# Sheet1.net
KiCad netlist of a schematic drawn in Altium Designer
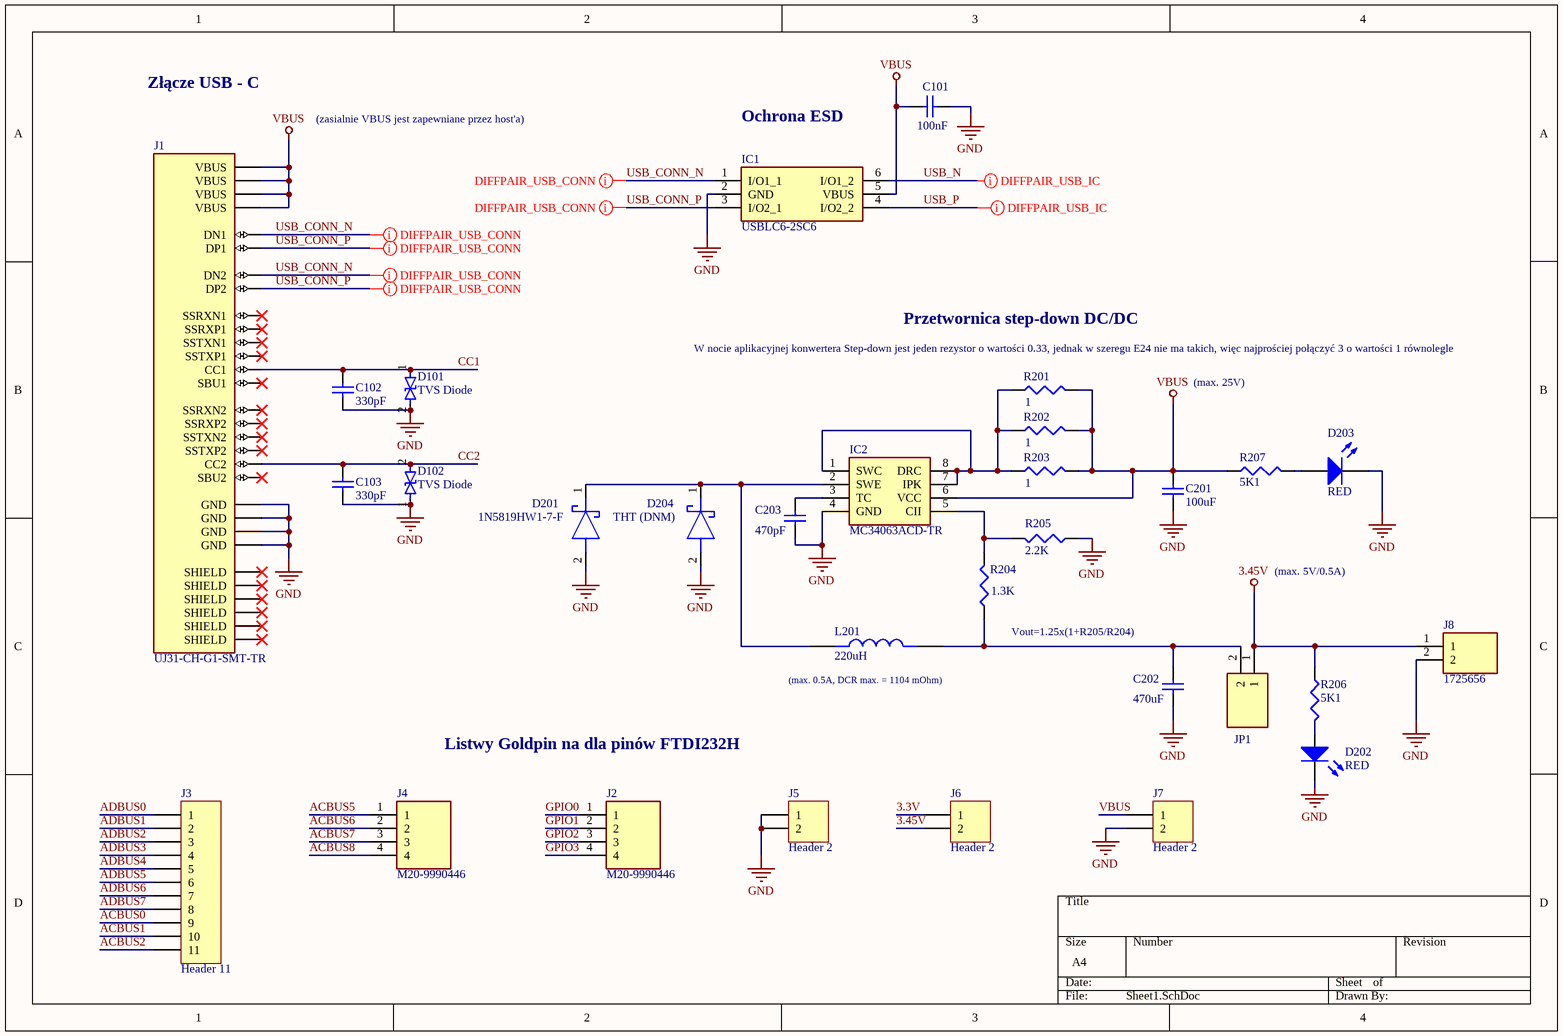
[diagram p0: Sheet1.SchDoc]

(export (version "E")
  (design (tool "Eeschema 10.0.6"))
  (components
    (comp (ref "C101")
      (value "100nF")
      (footprint "1608[0603]")
      (description "Capacitor (Semiconductor SIM Model)")
      (fields (field (name "Comment") "Cap Semi") (field (name "PUBLISHER") "Altium Limited"))
      (libsource (lib "Miscellaneous Devices") (part "Cap Semi"))
    )
    (comp (ref "C102")
      (value "330pF")
      (footprint "1608[0603]")
      (description "Capacitor (Semiconductor SIM Model)")
      (fields (field (name "Comment") "Cap Semi") (field (name "PUBLISHER") "Altium Limited"))
      (libsource (lib "Miscellaneous Devices") (part "Cap Semi"))
    )
    (comp (ref "C103")
      (value "330pF")
      (footprint "1608[0603]")
      (description "Capacitor (Semiconductor SIM Model)")
      (fields (field (name "Comment") "Cap Semi") (field (name "PUBLISHER") "Altium Limited"))
      (libsource (lib "Miscellaneous Devices") (part "Cap Semi"))
    )
    (comp (ref "C201")
      (value "100uF")
      (footprint "1608[0603]")
      (description "Capacitor (Semiconductor SIM Model)")
      (fields (field (name "Comment") "Cap Semi") (field (name "PUBLISHER") "Altium Limited"))
      (libsource (lib "Miscellaneous Devices") (part "Cap Semi"))
    )
    (comp (ref "C202")
      (value "470uF")
      (footprint "1608[0603]")
      (description "Capacitor (Semiconductor SIM Model)")
      (fields (field (name "Comment") "Cap Semi") (field (name "PUBLISHER") "Altium Limited"))
      (libsource (lib "Miscellaneous Devices") (part "Cap Semi"))
    )
    (comp (ref "C203")
      (value "470pF")
      (footprint "1608[0603]")
      (description "Capacitor (Semiconductor SIM Model)")
      (fields (field (name "Comment") "Cap Semi") (field (name "PUBLISHER") "Altium Limited"))
      (libsource (lib "Miscellaneous Devices") (part "Cap Semi"))
    )
    (comp (ref "D101")
      (value "TVS Diode")
      (footprint "PESD15VW1BCSF - TVS Diode")
      (description "PESD15VW1BCSFYL - Extremely low capacitance bidirectional ESD protection diode")
      (libsource (lib "Schlib1") (part "PESD15VW1BCSFYL"))
    )
    (comp (ref "D102")
      (value "TVS Diode")
      (footprint "PESD15VW1BCSF - TVS Diode")
      (description "PESD15VW1BCSFYL - Extremely low capacitance bidirectional ESD protection diode")
      (libsource (lib "Schlib1") (part "PESD15VW1BCSFYL"))
    )
    (comp (ref "D201")
      (value "1N5819HW1-7-F")
      (footprint "SODFL3518X115N")
      (description "Schottky Diode")
      (fields (field (name "MOUSER PART NUMBER") "621-1N5819HW1-7-F"))
      (libsource (lib "Schlib1") (part "1N5819HW1-7-F"))
    )
    (comp (ref "D202")
      (value "RED")
      (footprint "LEDC2012X80N")
      (description "Typical RED, GREEN, YELLOW, AMBER GaAs LED")
      (fields (field (name "PUBLISHER") "Altium Limited"))
      (libsource (lib "Miscellaneous Devices") (part "LED2"))
    )
    (comp (ref "D203")
      (value "RED")
      (footprint "LEDC2012X80N")
      (description "Typical RED, GREEN, YELLOW, AMBER GaAs LED")
      (fields (field (name "PUBLISHER") "Altium Limited"))
      (libsource (lib "Miscellaneous Devices") (part "LED2"))
    )
    (comp (ref "D204")
      (value "THT (DNM)")
      (footprint "DIOAD1796W86L628D292")
      (description "Schottky Diode")
      (fields
        (field (name "MANUFACTURER_PART_NUMBER") "1N5819HW1-7-F")
        (field (name "MOUSER PART NUMBER") "621-1N5819HW1-7-F")
      )
      (libsource (lib "Schlib1") (part "1N5819HW1-7-F"))
    )
    (comp (ref "IC1")
      (value "USBLC6-2SC6")
      (footprint "SOT95P280X145-6N")
      (description "Integrated Circuit")
      (fields (field (name "MOUSER PART NUMBER") "511-USBLC6-2SC6"))
      (libsource (lib "Schlib1") (part "USBLC6-2SC6"))
    )
    (comp (ref "IC2")
      (value "MC34063ACD-TR")
      (footprint "SOIC127P600X175-8N")
      (description "Integrated Circuit")
      (fields (field (name "MOUSER PART NUMBER") "511-MC34063ACD-TR"))
      (libsource (lib "Schlib1") (part "MC34063ACD-TR"))
    )
    (comp (ref "J1")
      (value "UJ31-CH-G1-SMT-TR")
      (footprint "CUI_UJ31-CH-G1-SMT-TR - duplicate")
      (description "Type C, USB 3.1 Gen 2, 5 A, Right Angle, Surface Mount _SMT_ , USB Receptacle")
      (fields (field (name "MF") "CUI Devices"))
      (libsource (lib "Schlib1") (part "UJ31-CH-G1-SMT-TR"))
    )
    (comp (ref "J2")
      (value "M20-9990446")
      (footprint "HDRV4W64P0X254_1X4_1016X254X889P")
      (description "Connector")
      (fields (field (name "MOUSER PART NUMBER") "855-M20-9990446"))
      (libsource (lib "Schlib1") (part "M20-9990446"))
    )
    (comp (ref "J3")
      (value "Header 11")
      (footprint "HDR1X11")
      (description "Header, 11-Pin")
      (fields (field (name "PUBLISHER") "Altium Limited"))
      (libsource (lib "Miscellaneous Connectors") (part "Header 11"))
    )
    (comp (ref "J4")
      (value "M20-9990446")
      (footprint "HDRV4W64P0X254_1X4_1016X254X889P")
      (description "Connector")
      (fields (field (name "MOUSER PART NUMBER") "855-M20-9990446"))
      (libsource (lib "Schlib1") (part "M20-9990446"))
    )
    (comp (ref "J5")
      (value "Header 2")
      (footprint "HDR1X2")
      (description "Header, 2-Pin")
      (fields (field (name "PUBLISHER") "Altium Limited"))
      (libsource (lib "Miscellaneous Connectors") (part "Header 2"))
    )
    (comp (ref "J6")
      (value "Header 2")
      (footprint "HDR1X2")
      (description "Header, 2-Pin")
      (fields (field (name "PUBLISHER") "Altium Limited"))
      (libsource (lib "Miscellaneous Connectors") (part "Header 2"))
    )
    (comp (ref "J7")
      (value "Header 2")
      (footprint "HDR1X2")
      (description "Header, 2-Pin")
      (fields (field (name "PUBLISHER") "Altium Limited"))
      (libsource (lib "Miscellaneous Connectors") (part "Header 2"))
    )
    (comp (ref "J8")
      (value "1725656")
      (footprint "SamacSys:1725656")
      (description "Screw terminal")
      (fields (field (name "MOUSER PART NUMBER") "651-1725656"))
      (libsource (lib "Schlib1") (part "1725656"))
    )
    (comp (ref "JP1")
      (value "5-146277-2")
      (footprint "HDRV2W67P0X254_1X2_467X234X823P")
      (description "Connector")
      (fields (field (name "MOUSER PART NUMBER") "571-5-146277-2"))
      (libsource (lib "Schlib1") (part "5-146277-2"))
    )
    (comp (ref "L201")
      (value "220uH")
      (footprint "242418 FPS")
      (description "Inductor 220uH, tolerance=20%, max. current=0.5A, DCR max. = 1104 mOhm")
      (libsource (lib "Schlib1") (part "242418FPS-221M-01"))
    )
    (comp (ref "R201")
      (value "1")
      (footprint "RESC1608X55N")
      (description "Resistor")
      (fields (field (name "Comment") "Res3") (field (name "PUBLISHER") "Altium Limited"))
      (libsource (lib "Miscellaneous Devices") (part "Res3"))
    )
    (comp (ref "R202")
      (value "1")
      (footprint "RESC1608X55N")
      (description "Resistor")
      (fields (field (name "Comment") "Res3") (field (name "PUBLISHER") "Altium Limited"))
      (libsource (lib "Miscellaneous Devices") (part "Res3"))
    )
    (comp (ref "R203")
      (value "1")
      (footprint "RESC1608X55N")
      (description "Resistor")
      (fields (field (name "Comment") "Res3") (field (name "PUBLISHER") "Altium Limited"))
      (libsource (lib "Miscellaneous Devices") (part "Res3"))
    )
    (comp (ref "R204")
      (value "1.3K")
      (footprint "RESC1608X55N")
      (description "Resistor")
      (fields (field (name "Comment") "Res3") (field (name "PUBLISHER") "Altium Limited"))
      (libsource (lib "Miscellaneous Devices") (part "Res3"))
    )
    (comp (ref "R205")
      (value "2.2K")
      (footprint "RESC1608X55N")
      (description "Resistor")
      (fields (field (name "Comment") "Res3") (field (name "PUBLISHER") "Altium Limited"))
      (libsource (lib "Miscellaneous Devices") (part "Res3"))
    )
    (comp (ref "R206")
      (value "5K1")
      (footprint "RESC1608X55N")
      (description "Resistor")
      (fields (field (name "Comment") "Res3") (field (name "PUBLISHER") "Altium Limited"))
      (libsource (lib "Miscellaneous Devices") (part "Res3"))
    )
    (comp (ref "R207")
      (value "5K1")
      (footprint "RESC1608X55N")
      (description "Resistor")
      (fields (field (name "Comment") "Res3") (field (name "PUBLISHER") "Altium Limited"))
      (libsource (lib "Miscellaneous Devices") (part "Res3"))
    )
  )
  (nets
    (net (code "1") (name "/3.3V") (class "Default")
      (node (ref "J6") (pin "1") (pinfunction "1_1") (pintype "passive"))
    )
    (net (code "2") (name "/ACBUS0") (class "Default")
      (node (ref "J3") (pin "9") (pinfunction "9_9") (pintype "passive"))
    )
    (net (code "3") (name "/ACBUS1") (class "Default")
      (node (ref "J3") (pin "10") (pinfunction "10_10") (pintype "passive"))
    )
    (net (code "4") (name "/ACBUS2") (class "Default")
      (node (ref "J3") (pin "11") (pinfunction "11_11") (pintype "passive"))
    )
    (net (code "5") (name "/ACBUS5") (class "Default")
      (node (ref "J4") (pin "1") (pinfunction "1_1") (pintype "passive"))
    )
    (net (code "6") (name "/ACBUS6") (class "Default")
      (node (ref "J4") (pin "2") (pinfunction "2_2") (pintype "passive"))
    )
    (net (code "7") (name "/ACBUS7") (class "Default")
      (node (ref "J4") (pin "3") (pinfunction "3_3") (pintype "passive"))
    )
    (net (code "8") (name "/ACBUS8") (class "Default")
      (node (ref "J4") (pin "4") (pinfunction "4_4") (pintype "passive"))
    )
    (net (code "9") (name "/ADBUS0") (class "Default")
      (node (ref "J3") (pin "1") (pinfunction "1_1") (pintype "passive"))
    )
    (net (code "10") (name "/ADBUS1") (class "Default")
      (node (ref "J3") (pin "2") (pinfunction "2_2") (pintype "passive"))
    )
    (net (code "11") (name "/ADBUS2") (class "Default")
      (node (ref "J3") (pin "3") (pinfunction "3_3") (pintype "passive"))
    )
    (net (code "12") (name "/ADBUS3") (class "Default")
      (node (ref "J3") (pin "4") (pinfunction "4_4") (pintype "passive"))
    )
    (net (code "13") (name "/ADBUS4") (class "Default")
      (node (ref "J3") (pin "5") (pinfunction "5_5") (pintype "passive"))
    )
    (net (code "14") (name "/ADBUS5") (class "Default")
      (node (ref "J3") (pin "6") (pinfunction "6_6") (pintype "passive"))
    )
    (net (code "15") (name "/ADBUS6") (class "Default")
      (node (ref "J3") (pin "7") (pinfunction "7_7") (pintype "passive"))
    )
    (net (code "16") (name "/ADBUS7") (class "Default")
      (node (ref "J3") (pin "8") (pinfunction "8_8") (pintype "passive"))
    )
    (net (code "17") (name "/CC1") (class "Default")
      (node (ref "C102") (pin "2") (pinfunction "2_2") (pintype "passive"))
      (node (ref "D101") (pin "1") (pintype "passive"))
      (node (ref "J1") (pin "A5") (pinfunction "CC1_A5") (pintype "bidirectional"))
    )
    (net (code "18") (name "/CC2") (class "Default")
      (node (ref "C103") (pin "2") (pinfunction "2_2") (pintype "passive"))
      (node (ref "D102") (pin "2") (pintype "passive"))
      (node (ref "J1") (pin "B5") (pinfunction "CC2_B5") (pintype "bidirectional"))
    )
    (net (code "19") (name "/GPIO0") (class "Default")
      (node (ref "J2") (pin "1") (pinfunction "1_1") (pintype "passive"))
    )
    (net (code "20") (name "/GPIO1") (class "Default")
      (node (ref "J2") (pin "2") (pinfunction "2_2") (pintype "passive"))
    )
    (net (code "21") (name "/GPIO2") (class "Default")
      (node (ref "J2") (pin "3") (pinfunction "3_3") (pintype "passive"))
    )
    (net (code "22") (name "/GPIO3") (class "Default")
      (node (ref "J2") (pin "4") (pinfunction "4_4") (pintype "passive"))
    )
    (net (code "23") (name "/USB_CONN_N") (class "Default")
      (node (ref "IC1") (pin "1") (pinfunction "I/O1_1_1") (pintype "passive"))
      (node (ref "J1") (pin "A7") (pinfunction "DN1_A7") (pintype "bidirectional"))
      (node (ref "J1") (pin "B7") (pinfunction "DN2_B7") (pintype "bidirectional"))
    )
    (net (code "24") (name "/USB_CONN_P") (class "Default")
      (node (ref "IC1") (pin "3") (pinfunction "I/O2_1_3") (pintype "passive"))
      (node (ref "J1") (pin "A6") (pinfunction "DP1_A6") (pintype "bidirectional"))
      (node (ref "J1") (pin "B6") (pinfunction "DP2_B6") (pintype "bidirectional"))
    )
    (net (code "25") (name "/USB_N") (class "Default")
      (node (ref "IC1") (pin "6") (pinfunction "I/O1_2_6") (pintype "passive"))
    )
    (net (code "26") (name "/USB_P") (class "Default")
      (node (ref "IC1") (pin "4") (pinfunction "I/O2_2_4") (pintype "passive"))
    )
    (net (code "27") (name "3.45V") (class "Default")
      (node (ref "J6") (pin "2") (pinfunction "2_2") (pintype "passive"))
      (node (ref "J8") (pin "1") (pinfunction "1_1") (pintype "passive"))
      (node (ref "JP1") (pin "1") (pinfunction "1_1") (pintype "passive"))
      (node (ref "R206") (pin "1") (pinfunction "1_1") (pintype "passive"))
    )
    (net (code "28") (name "GND") (class "Default")
      (node (ref "C101") (pin "2") (pinfunction "2_2") (pintype "passive"))
      (node (ref "C102") (pin "1") (pinfunction "1_1") (pintype "passive"))
      (node (ref "C103") (pin "1") (pinfunction "1_1") (pintype "passive"))
      (node (ref "C201") (pin "1") (pinfunction "1_1") (pintype "passive"))
      (node (ref "C202") (pin "1") (pinfunction "1_1") (pintype "passive"))
      (node (ref "C203") (pin "1") (pinfunction "1_1") (pintype "passive"))
      (node (ref "D101") (pin "2") (pintype "passive"))
      (node (ref "D102") (pin "1") (pintype "passive"))
      (node (ref "D201") (pin "2") (pinfunction "A_2") (pintype "passive"))
      (node (ref "D202") (pin "2") (pinfunction "K_2") (pintype "passive"))
      (node (ref "D203") (pin "2") (pinfunction "K_2") (pintype "passive"))
      (node (ref "D204") (pin "2") (pinfunction "A_2") (pintype "passive"))
      (node (ref "IC1") (pin "2") (pinfunction "GND_2") (pintype "passive"))
      (node (ref "IC2") (pin "4") (pinfunction "GND_4") (pintype "passive"))
      (node (ref "J1") (pin "A1") (pinfunction "GND_A1") (pintype "power_in"))
      (node (ref "J1") (pin "A12") (pinfunction "GND_A12") (pintype "power_in"))
      (node (ref "J1") (pin "B1") (pinfunction "GND_B1") (pintype "power_in"))
      (node (ref "J1") (pin "B12") (pinfunction "GND_B12") (pintype "power_in"))
      (node (ref "J5") (pin "1") (pinfunction "1_1") (pintype "passive"))
      (node (ref "J5") (pin "2") (pinfunction "2_2") (pintype "passive"))
      (node (ref "J7") (pin "2") (pinfunction "2_2") (pintype "passive"))
      (node (ref "J8") (pin "2") (pinfunction "2_2") (pintype "passive"))
      (node (ref "R205") (pin "1") (pinfunction "1_1") (pintype "passive"))
    )
    (net (code "29") (name "Net-(C202-Pad2)") (class "Default")
      (node (ref "C202") (pin "2") (pinfunction "2_2") (pintype "passive"))
      (node (ref "JP1") (pin "2") (pinfunction "2_2") (pintype "passive"))
      (node (ref "L201") (pin "2") (pinfunction "2_2") (pintype "passive"))
      (node (ref "R204") (pin "1") (pinfunction "1_1") (pintype "passive"))
    )
    (net (code "30") (name "Net-(D201-K)") (class "Default")
      (node (ref "D201") (pin "1") (pinfunction "K_1") (pintype "passive"))
      (node (ref "D204") (pin "1") (pinfunction "K_1") (pintype "passive"))
      (node (ref "IC2") (pin "2") (pinfunction "SWE_2") (pintype "passive"))
      (node (ref "L201") (pin "1") (pinfunction "1_1") (pintype "passive"))
    )
    (net (code "31") (name "Net-(D202-A)") (class "Default")
      (node (ref "D202") (pin "1") (pinfunction "A_1") (pintype "passive"))
      (node (ref "R206") (pin "2") (pinfunction "2_2") (pintype "passive"))
    )
    (net (code "32") (name "Net-(D203-A)") (class "Default")
      (node (ref "D203") (pin "1") (pinfunction "A_1") (pintype "passive"))
      (node (ref "R207") (pin "2") (pinfunction "2_2") (pintype "passive"))
    )
    (net (code "33") (name "Net-(IC2-CII)") (class "Default")
      (node (ref "IC2") (pin "5") (pinfunction "CII_5") (pintype "passive"))
      (node (ref "R204") (pin "2") (pinfunction "2_2") (pintype "passive"))
      (node (ref "R205") (pin "2") (pinfunction "2_2") (pintype "passive"))
    )
    (net (code "34") (name "Net-(IC2-DRC)") (class "Default")
      (node (ref "IC2") (pin "1") (pinfunction "SWC_1") (pintype "passive"))
      (node (ref "IC2") (pin "7") (pinfunction "IPK_7") (pintype "passive"))
      (node (ref "IC2") (pin "8") (pinfunction "DRC_8") (pintype "passive"))
      (node (ref "R201") (pin "1") (pinfunction "1_1") (pintype "passive"))
      (node (ref "R202") (pin "1") (pinfunction "1_1") (pintype "passive"))
      (node (ref "R203") (pin "1") (pinfunction "1_1") (pintype "passive"))
    )
    (net (code "35") (name "Net-(IC2-TC)") (class "Default")
      (node (ref "C203") (pin "2") (pinfunction "2_2") (pintype "passive"))
      (node (ref "IC2") (pin "3") (pinfunction "TC_3") (pintype "passive"))
    )
    (net (code "36") (name "VBUS") (class "Default")
      (node (ref "C101") (pin "1") (pinfunction "1_1") (pintype "passive"))
      (node (ref "C201") (pin "2") (pinfunction "2_2") (pintype "passive"))
      (node (ref "IC1") (pin "5") (pinfunction "VBUS_5") (pintype "passive"))
      (node (ref "IC2") (pin "6") (pinfunction "VCC_6") (pintype "passive"))
      (node (ref "J1") (pin "A4") (pinfunction "VBUS_A4") (pintype "power_in"))
      (node (ref "J1") (pin "A9") (pinfunction "VBUS_A9") (pintype "power_in"))
      (node (ref "J1") (pin "B4") (pinfunction "VBUS_B4") (pintype "power_in"))
      (node (ref "J1") (pin "B9") (pinfunction "VBUS_B9") (pintype "power_in"))
      (node (ref "J7") (pin "1") (pinfunction "1_1") (pintype "passive"))
      (node (ref "R201") (pin "2") (pinfunction "2_2") (pintype "passive"))
      (node (ref "R202") (pin "2") (pinfunction "2_2") (pintype "passive"))
      (node (ref "R203") (pin "2") (pinfunction "2_2") (pintype "passive"))
      (node (ref "R207") (pin "1") (pinfunction "1_1") (pintype "passive"))
    )
    (net (code "37") (name "unconnected-(J1-SBU1-PadA8)") (class "Default")
      (node (ref "J1") (pin "A8") (pinfunction "SBU1_A8") (pintype "bidirectional+no_connect"))
    )
    (net (code "38") (name "unconnected-(J1-SBU2-PadB8)") (class "Default")
      (node (ref "J1") (pin "B8") (pinfunction "SBU2_B8") (pintype "bidirectional+no_connect"))
    )
    (net (code "39") (name "unconnected-(J1-SHIELD-PadSH1)") (class "Default")
      (node (ref "J1") (pin "SH1") (pinfunction "SHIELD_SH1") (pintype "power_in+no_connect"))
    )
    (net (code "40") (name "unconnected-(J1-SHIELD-PadSH2)") (class "Default")
      (node (ref "J1") (pin "SH2") (pinfunction "SHIELD_SH2") (pintype "power_in+no_connect"))
    )
    (net (code "41") (name "unconnected-(J1-SHIELD-PadSH3)") (class "Default")
      (node (ref "J1") (pin "SH3") (pinfunction "SHIELD_SH3") (pintype "power_in+no_connect"))
    )
    (net (code "42") (name "unconnected-(J1-SHIELD-PadSH4)") (class "Default")
      (node (ref "J1") (pin "SH4") (pinfunction "SHIELD_SH4") (pintype "power_in+no_connect"))
    )
    (net (code "43") (name "unconnected-(J1-SHIELD-PadSH5)") (class "Default")
      (node (ref "J1") (pin "SH5") (pinfunction "SHIELD_SH5") (pintype "power_in+no_connect"))
    )
    (net (code "44") (name "unconnected-(J1-SHIELD-PadSH6)") (class "Default")
      (node (ref "J1") (pin "SH6") (pinfunction "SHIELD_SH6") (pintype "power_in+no_connect"))
    )
    (net (code "45") (name "unconnected-(J1-SSRXN1-PadB10)") (class "Default")
      (node (ref "J1") (pin "B10") (pinfunction "SSRXN1_B10") (pintype "bidirectional+no_connect"))
    )
    (net (code "46") (name "unconnected-(J1-SSRXN2-PadA10)") (class "Default")
      (node (ref "J1") (pin "A10") (pinfunction "SSRXN2_A10") (pintype "bidirectional+no_connect"))
    )
    (net (code "47") (name "unconnected-(J1-SSRXP1-PadB11)") (class "Default")
      (node (ref "J1") (pin "B11") (pinfunction "SSRXP1_B11") (pintype "bidirectional+no_connect"))
    )
    (net (code "48") (name "unconnected-(J1-SSRXP2-PadA11)") (class "Default")
      (node (ref "J1") (pin "A11") (pinfunction "SSRXP2_A11") (pintype "bidirectional+no_connect"))
    )
    (net (code "49") (name "unconnected-(J1-SSTXN1-PadA3)") (class "Default")
      (node (ref "J1") (pin "A3") (pinfunction "SSTXN1_A3") (pintype "bidirectional+no_connect"))
    )
    (net (code "50") (name "unconnected-(J1-SSTXN2-PadB3)") (class "Default")
      (node (ref "J1") (pin "B3") (pinfunction "SSTXN2_B3") (pintype "bidirectional+no_connect"))
    )
    (net (code "51") (name "unconnected-(J1-SSTXP1-PadA2)") (class "Default")
      (node (ref "J1") (pin "A2") (pinfunction "SSTXP1_A2") (pintype "bidirectional+no_connect"))
    )
    (net (code "52") (name "unconnected-(J1-SSTXP2-PadB2)") (class "Default")
      (node (ref "J1") (pin "B2") (pinfunction "SSTXP2_B2") (pintype "bidirectional+no_connect"))
    )
  )
)
